# ledboard_segment.net
KiCad netlist of a schematic drawn in EAGLE
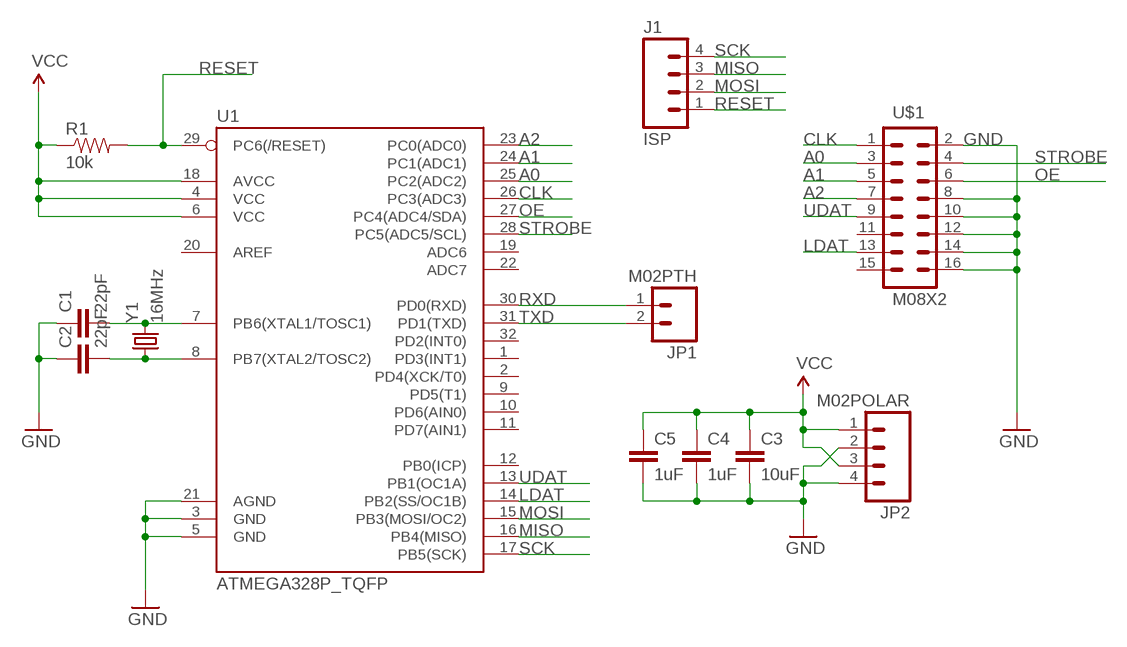
[diagram p0: schematic, sheet 1]

(export (version "E")
  (design (tool "Eeschema 10.0.6"))
  (components
    (comp (ref "C1")
      (value "22pF")
      (footprint "eagle-import:0805")
      (libsource (lib "eagle-import") (part "CAP0805"))
    )
    (comp (ref "C2")
      (value "22pF")
      (footprint "eagle-import:0805")
      (libsource (lib "eagle-import") (part "CAP0805"))
    )
    (comp (ref "C3")
      (value "10uF")
      (footprint "eagle-import:0805")
      (libsource (lib "eagle-import") (part "CAP0805"))
    )
    (comp (ref "C4")
      (value "1uF")
      (footprint "eagle-import:0805")
      (libsource (lib "eagle-import") (part "CAP0805"))
    )
    (comp (ref "C5")
      (value "1uF")
      (footprint "eagle-import:0805")
      (libsource (lib "eagle-import") (part "CAP0805"))
    )
    (comp (ref "J1")
      (value "ISP")
      (footprint "eagle-import:1X04")
      (libsource (lib "eagle-import") (part "M04PTH"))
    )
    (comp (ref "JP1")
      (value "M02PTH")
      (footprint "eagle-import:1X02")
      (libsource (lib "eagle-import") (part "M02PTH"))
    )
    (comp (ref "JP2")
      (value "M02POLAR")
      (footprint "eagle-import:1X04_NO_SILK")
      (libsource (lib "eagle-import") (part "M041X04_NO_SILK"))
    )
    (comp (ref "R1")
      (value "10k")
      (footprint "eagle-import:0805")
      (libsource (lib "eagle-import") (part "RESISTOR0805-RES"))
    )
    (comp (ref "U$1")
      (value "M08X2")
      (footprint "eagle-import:2X8")
      (libsource (lib "eagle-import") (part "M08X2"))
    )
    (comp (ref "U1")
      (value "ATMEGA328P_TQFP")
      (footprint "eagle-import:TQFP32-08")
      (libsource (lib "eagle-import") (part "ATMEGA328P_TQFP"))
    )
    (comp (ref "Y1")
      (value "16MHz")
      (footprint "eagle-import:CRYSTAL-TXC-7A")
      (libsource (lib "eagle-import") (part "CRYSTALTXC-7A"))
    )
  )
  (nets
    (net (code "1") (name "/A0") (class "Default")
      (node (ref "U$1") (pin "3") (pinfunction "3_3") (pintype "passive"))
      (node (ref "U1") (pin "25") (pinfunction "PC2(ADC2)_25") (pintype "bidirectional"))
    )
    (net (code "2") (name "/A1") (class "Default")
      (node (ref "U$1") (pin "5") (pinfunction "5_5") (pintype "passive"))
      (node (ref "U1") (pin "24") (pinfunction "PC1(ADC1)_24") (pintype "bidirectional"))
    )
    (net (code "3") (name "/A2") (class "Default")
      (node (ref "U$1") (pin "7") (pinfunction "7_7") (pintype "passive"))
      (node (ref "U1") (pin "23") (pinfunction "PC0(ADC0)_23") (pintype "bidirectional"))
    )
    (net (code "4") (name "/CLK") (class "Default")
      (node (ref "U$1") (pin "1") (pinfunction "1_1") (pintype "passive"))
      (node (ref "U1") (pin "26") (pinfunction "PC3(ADC3)_26") (pintype "bidirectional"))
    )
    (net (code "5") (name "/LDAT") (class "Default")
      (node (ref "U$1") (pin "13") (pinfunction "13_13") (pintype "passive"))
      (node (ref "U1") (pin "14") (pinfunction "PB2(SS/OC1B)_14") (pintype "bidirectional"))
    )
    (net (code "6") (name "/MISO") (class "Default")
      (node (ref "J1") (pin "3") (pinfunction "3_3") (pintype "passive"))
      (node (ref "U1") (pin "16") (pinfunction "PB4(MISO)_16") (pintype "bidirectional"))
    )
    (net (code "7") (name "/MOSI") (class "Default")
      (node (ref "J1") (pin "2") (pinfunction "2_2") (pintype "passive"))
      (node (ref "U1") (pin "15") (pinfunction "PB3(MOSI/OC2)_15") (pintype "bidirectional"))
    )
    (net (code "8") (name "/OE") (class "Default")
      (node (ref "U$1") (pin "6") (pinfunction "6_6") (pintype "passive"))
      (node (ref "U1") (pin "27") (pinfunction "PC4(ADC4/SDA)_27") (pintype "bidirectional"))
    )
    (net (code "9") (name "/RESET") (class "Default")
      (node (ref "J1") (pin "1") (pinfunction "1_1") (pintype "passive"))
      (node (ref "R1") (pin "2") (pinfunction "2_2") (pintype "passive"))
      (node (ref "U1") (pin "29") (pinfunction "PC6(/RESET)_29") (pintype "bidirectional"))
    )
    (net (code "10") (name "/RXD") (class "Default")
      (node (ref "JP1") (pin "1") (pinfunction "1_1") (pintype "passive"))
      (node (ref "U1") (pin "30") (pinfunction "PD0(RXD)_30") (pintype "bidirectional"))
    )
    (net (code "11") (name "/SCK") (class "Default")
      (node (ref "J1") (pin "4") (pinfunction "4_4") (pintype "passive"))
      (node (ref "U1") (pin "17") (pinfunction "PB5(SCK)_17") (pintype "bidirectional"))
    )
    (net (code "12") (name "/STROBE") (class "Default")
      (node (ref "U$1") (pin "4") (pinfunction "4_4") (pintype "passive"))
      (node (ref "U1") (pin "28") (pinfunction "PC5(ADC5/SCL)_28") (pintype "bidirectional"))
    )
    (net (code "13") (name "/TXD") (class "Default")
      (node (ref "JP1") (pin "2") (pinfunction "2_2") (pintype "passive"))
      (node (ref "U1") (pin "31") (pinfunction "PD1(TXD)_31") (pintype "bidirectional"))
    )
    (net (code "14") (name "/UDAT") (class "Default")
      (node (ref "U$1") (pin "9") (pinfunction "9_9") (pintype "passive"))
      (node (ref "U1") (pin "13") (pinfunction "PB1(OC1A)_13") (pintype "bidirectional"))
    )
    (net (code "15") (name "GND") (class "Default")
      (node (ref "C1") (pin "1") (pinfunction "1_1") (pintype "passive"))
      (node (ref "C2") (pin "1") (pinfunction "1_1") (pintype "passive"))
      (node (ref "C3") (pin "2") (pinfunction "2_2") (pintype "passive"))
      (node (ref "C4") (pin "2") (pinfunction "2_2") (pintype "passive"))
      (node (ref "C5") (pin "2") (pinfunction "2_2") (pintype "passive"))
      (node (ref "JP2") (pin "2") (pinfunction "2_2") (pintype "passive"))
      (node (ref "JP2") (pin "4") (pinfunction "4_4") (pintype "passive"))
      (node (ref "U$1") (pin "10") (pinfunction "10_10") (pintype "passive"))
      (node (ref "U$1") (pin "12") (pinfunction "12_12") (pintype "passive"))
      (node (ref "U$1") (pin "14") (pinfunction "14_14") (pintype "passive"))
      (node (ref "U$1") (pin "16") (pinfunction "16_16") (pintype "passive"))
      (node (ref "U$1") (pin "2") (pinfunction "2_2") (pintype "passive"))
      (node (ref "U$1") (pin "8") (pinfunction "8_8") (pintype "passive"))
      (node (ref "U1") (pin "21") (pinfunction "AGND_21") (pintype "bidirectional"))
      (node (ref "U1") (pin "3") (pinfunction "GND_3") (pintype "bidirectional"))
      (node (ref "U1") (pin "5") (pinfunction "GND_5") (pintype "bidirectional"))
    )
    (net (code "16") (name "Net-(U1-PB6(XTAL1{slash}TOSC1))") (class "Default")
      (node (ref "C1") (pin "2") (pinfunction "2_2") (pintype "passive"))
      (node (ref "U1") (pin "7") (pinfunction "PB6(XTAL1/TOSC1)_7") (pintype "bidirectional"))
      (node (ref "Y1") (pin "P$2") (pinfunction "2_P$2") (pintype "passive"))
    )
    (net (code "17") (name "Net-(U1-PB7(XTAL2{slash}TOSC2))") (class "Default")
      (node (ref "C2") (pin "2") (pinfunction "2_2") (pintype "passive"))
      (node (ref "U1") (pin "8") (pinfunction "PB7(XTAL2/TOSC2)_8") (pintype "bidirectional"))
      (node (ref "Y1") (pin "P$1") (pinfunction "1_P$1") (pintype "passive"))
    )
    (net (code "18") (name "VCC") (class "Default")
      (node (ref "C3") (pin "1") (pinfunction "1_1") (pintype "passive"))
      (node (ref "C4") (pin "1") (pinfunction "1_1") (pintype "passive"))
      (node (ref "C5") (pin "1") (pinfunction "1_1") (pintype "passive"))
      (node (ref "JP2") (pin "1") (pinfunction "1_1") (pintype "passive"))
      (node (ref "JP2") (pin "3") (pinfunction "3_3") (pintype "passive"))
      (node (ref "R1") (pin "1") (pinfunction "1_1") (pintype "passive"))
      (node (ref "U1") (pin "18") (pinfunction "AVCC_18") (pintype "bidirectional"))
      (node (ref "U1") (pin "4") (pinfunction "VCC_4") (pintype "bidirectional"))
      (node (ref "U1") (pin "6") (pinfunction "VCC_6") (pintype "bidirectional"))
    )
    (net (code "19") (name "unconnected-(U$1-Pad11)") (class "Default")
      (node (ref "U$1") (pin "11") (pinfunction "11_11") (pintype "passive"))
    )
    (net (code "20") (name "unconnected-(U$1-Pad15)") (class "Default")
      (node (ref "U$1") (pin "15") (pinfunction "15_15") (pintype "passive"))
    )
    (net (code "21") (name "unconnected-(U1-ADC6-Pad19)") (class "Default")
      (node (ref "U1") (pin "19") (pinfunction "ADC6_19") (pintype "bidirectional"))
    )
    (net (code "22") (name "unconnected-(U1-ADC7-Pad22)") (class "Default")
      (node (ref "U1") (pin "22") (pinfunction "ADC7_22") (pintype "bidirectional"))
    )
    (net (code "23") (name "unconnected-(U1-AREF-Pad20)") (class "Default")
      (node (ref "U1") (pin "20") (pinfunction "AREF_20") (pintype "bidirectional"))
    )
    (net (code "24") (name "unconnected-(U1-PB0(ICP)-Pad12)") (class "Default")
      (node (ref "U1") (pin "12") (pinfunction "PB0(ICP)_12") (pintype "bidirectional"))
    )
    (net (code "25") (name "unconnected-(U1-PD2(INT0)-Pad32)") (class "Default")
      (node (ref "U1") (pin "32") (pinfunction "PD2(INT0)_32") (pintype "bidirectional"))
    )
    (net (code "26") (name "unconnected-(U1-PD3(INT1)-Pad1)") (class "Default")
      (node (ref "U1") (pin "1") (pinfunction "PD3(INT1)_1") (pintype "bidirectional"))
    )
    (net (code "27") (name "unconnected-(U1-PD4(XCK{slash}T0)-Pad2)") (class "Default")
      (node (ref "U1") (pin "2") (pinfunction "PD4(XCK/T0)_2") (pintype "bidirectional"))
    )
    (net (code "28") (name "unconnected-(U1-PD5(T1)-Pad9)") (class "Default")
      (node (ref "U1") (pin "9") (pinfunction "PD5(T1)_9") (pintype "bidirectional"))
    )
    (net (code "29") (name "unconnected-(U1-PD6(AIN0)-Pad10)") (class "Default")
      (node (ref "U1") (pin "10") (pinfunction "PD6(AIN0)_10") (pintype "bidirectional"))
    )
    (net (code "30") (name "unconnected-(U1-PD7(AIN1)-Pad11)") (class "Default")
      (node (ref "U1") (pin "11") (pinfunction "PD7(AIN1)_11") (pintype "bidirectional"))
    )
  )
)
